# lcd-bracket.net
KiCad netlist of a schematic drawn in EAGLE
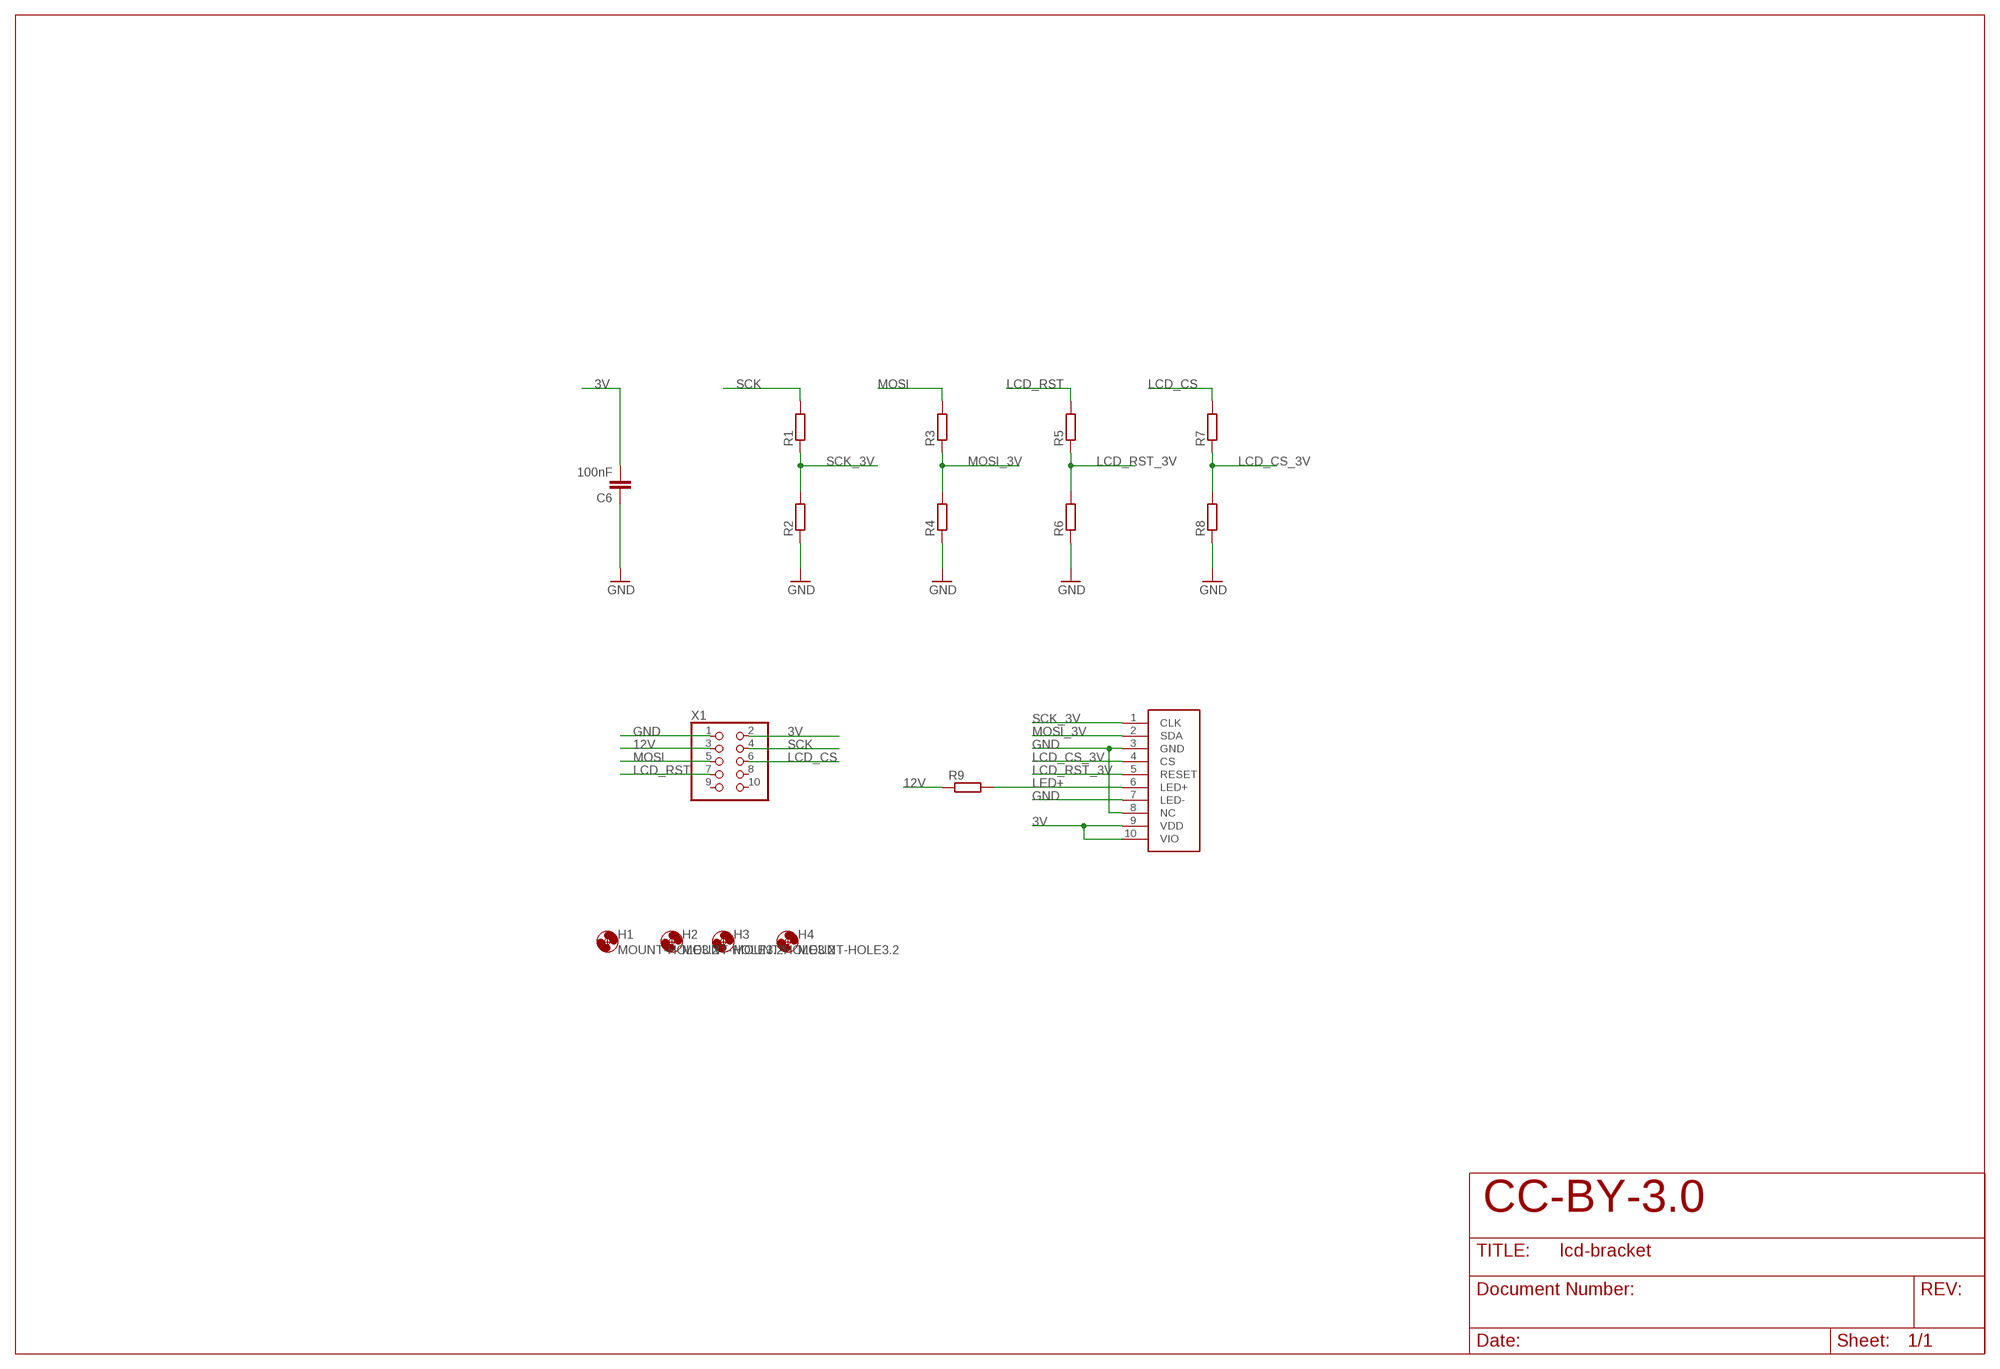
[diagram p0: schematic, sheet 1]

(export (version "E")
  (design (tool "Eeschema 10.0.6"))
  (components
    (comp (ref "C6")
      (value "100nF")
      (footprint "eagle-import:C0603K")
      (libsource (lib "eagle-import") (part "C-EUC0603K"))
    )
    (comp (ref "H1")
      (value "MOUNT-HOLE3.2")
      (footprint "eagle-import:3,2")
      (libsource (lib "eagle-import") (part "MOUNT-HOLE3.2"))
    )
    (comp (ref "H2")
      (value "MOUNT-HOLE3.2")
      (footprint "eagle-import:3,2")
      (libsource (lib "eagle-import") (part "MOUNT-HOLE3.2"))
    )
    (comp (ref "H3")
      (value "MOUNT-HOLE3.2")
      (footprint "eagle-import:3,2")
      (libsource (lib "eagle-import") (part "MOUNT-HOLE3.2"))
    )
    (comp (ref "H4")
      (value "MOUNT-HOLE3.2")
      (footprint "eagle-import:3,2")
      (libsource (lib "eagle-import") (part "MOUNT-HOLE3.2"))
    )
    (comp (ref "R1")
      (value "R-EU_R0603")
      (footprint "eagle-import:R0603")
      (libsource (lib "eagle-import") (part "R-EU_R0603"))
    )
    (comp (ref "R2")
      (value "R-EU_R0603")
      (footprint "eagle-import:R0603")
      (libsource (lib "eagle-import") (part "R-EU_R0603"))
    )
    (comp (ref "R3")
      (value "R-EU_R0603")
      (footprint "eagle-import:R0603")
      (libsource (lib "eagle-import") (part "R-EU_R0603"))
    )
    (comp (ref "R4")
      (value "R-EU_R0603")
      (footprint "eagle-import:R0603")
      (libsource (lib "eagle-import") (part "R-EU_R0603"))
    )
    (comp (ref "R5")
      (value "R-EU_R0603")
      (footprint "eagle-import:R0603")
      (libsource (lib "eagle-import") (part "R-EU_R0603"))
    )
    (comp (ref "R6")
      (value "R-EU_R0603")
      (footprint "eagle-import:R0603")
      (libsource (lib "eagle-import") (part "R-EU_R0603"))
    )
    (comp (ref "R7")
      (value "R-EU_R0603")
      (footprint "eagle-import:R0603")
      (libsource (lib "eagle-import") (part "R-EU_R0603"))
    )
    (comp (ref "R8")
      (value "R-EU_R0603")
      (footprint "eagle-import:R0603")
      (libsource (lib "eagle-import") (part "R-EU_R0603"))
    )
    (comp (ref "R9")
      (value "R-EU_R1206")
      (footprint "eagle-import:R1206")
      (libsource (lib "eagle-import") (part "R-EU_R1206"))
    )
    (comp (ref "X1")
      (value "PINHD-2X5")
      (footprint "eagle-import:2X05")
      (libsource (lib "eagle-import") (part "PINHD-2X5"))
    )
    (comp (ref "X2")
      (value "NOKIA")
      (footprint "eagle-import:DF23")
      (libsource (lib "eagle-import") (part "NOKIA"))
    )
  )
  (nets
    (net (code "1") (name "/3V") (class "Default")
      (node (ref "C6") (pin "2") (pinfunction "2_2") (pintype "passive"))
      (node (ref "X1") (pin "2") (pinfunction "2_2") (pintype "passive"))
      (node (ref "X2") (pin "10") (pinfunction "VIO_10") (pintype "bidirectional"))
      (node (ref "X2") (pin "9") (pinfunction "VDD_9") (pintype "bidirectional"))
    )
    (net (code "2") (name "/12V") (class "Default")
      (node (ref "R9") (pin "1") (pinfunction "1_1") (pintype "passive"))
      (node (ref "X1") (pin "3") (pinfunction "3_3") (pintype "passive"))
    )
    (net (code "3") (name "/LCD_CS") (class "Default")
      (node (ref "R7") (pin "2") (pinfunction "2_2") (pintype "passive"))
      (node (ref "X1") (pin "6") (pinfunction "6_6") (pintype "passive"))
    )
    (net (code "4") (name "/LCD_CS_3V") (class "Default")
      (node (ref "R7") (pin "1") (pinfunction "1_1") (pintype "passive"))
      (node (ref "R8") (pin "2") (pinfunction "2_2") (pintype "passive"))
      (node (ref "X2") (pin "4") (pinfunction "CS_4") (pintype "bidirectional"))
    )
    (net (code "5") (name "/LCD_RST") (class "Default")
      (node (ref "R5") (pin "2") (pinfunction "2_2") (pintype "passive"))
      (node (ref "X1") (pin "7") (pinfunction "7_7") (pintype "passive"))
    )
    (net (code "6") (name "/LCD_RST_3V") (class "Default")
      (node (ref "R5") (pin "1") (pinfunction "1_1") (pintype "passive"))
      (node (ref "R6") (pin "2") (pinfunction "2_2") (pintype "passive"))
      (node (ref "X2") (pin "5") (pinfunction "RESET_5") (pintype "bidirectional"))
    )
    (net (code "7") (name "/LED+") (class "Default")
      (node (ref "R9") (pin "2") (pinfunction "2_2") (pintype "passive"))
      (node (ref "X2") (pin "6") (pinfunction "LED+_6") (pintype "bidirectional"))
    )
    (net (code "8") (name "/MOSI") (class "Default")
      (node (ref "R3") (pin "2") (pinfunction "2_2") (pintype "passive"))
      (node (ref "X1") (pin "5") (pinfunction "5_5") (pintype "passive"))
    )
    (net (code "9") (name "/MOSI_3V") (class "Default")
      (node (ref "R3") (pin "1") (pinfunction "1_1") (pintype "passive"))
      (node (ref "R4") (pin "2") (pinfunction "2_2") (pintype "passive"))
      (node (ref "X2") (pin "2") (pinfunction "SDA_2") (pintype "bidirectional"))
    )
    (net (code "10") (name "/SCK") (class "Default")
      (node (ref "R1") (pin "2") (pinfunction "2_2") (pintype "passive"))
      (node (ref "X1") (pin "4") (pinfunction "4_4") (pintype "passive"))
    )
    (net (code "11") (name "/SCK_3V") (class "Default")
      (node (ref "R1") (pin "1") (pinfunction "1_1") (pintype "passive"))
      (node (ref "R2") (pin "2") (pinfunction "2_2") (pintype "passive"))
      (node (ref "X2") (pin "1") (pinfunction "CLK_1") (pintype "bidirectional"))
    )
    (net (code "12") (name "GND") (class "Default")
      (node (ref "C6") (pin "1") (pinfunction "1_1") (pintype "passive"))
      (node (ref "R2") (pin "1") (pinfunction "1_1") (pintype "passive"))
      (node (ref "R4") (pin "1") (pinfunction "1_1") (pintype "passive"))
      (node (ref "R6") (pin "1") (pinfunction "1_1") (pintype "passive"))
      (node (ref "R8") (pin "1") (pinfunction "1_1") (pintype "passive"))
      (node (ref "X1") (pin "1") (pinfunction "1_1") (pintype "passive"))
      (node (ref "X2") (pin "3") (pinfunction "GND_3") (pintype "bidirectional"))
      (node (ref "X2") (pin "7") (pinfunction "LED-_7") (pintype "bidirectional"))
      (node (ref "X2") (pin "8") (pinfunction "NC_8") (pintype "bidirectional"))
    )
    (net (code "13") (name "unconnected-(X1-Pad8)") (class "Default")
      (node (ref "X1") (pin "8") (pinfunction "8_8") (pintype "passive"))
    )
    (net (code "14") (name "unconnected-(X1-Pad9)") (class "Default")
      (node (ref "X1") (pin "9") (pinfunction "9_9") (pintype "passive"))
    )
    (net (code "15") (name "unconnected-(X1-Pad10)") (class "Default")
      (node (ref "X1") (pin "10") (pinfunction "10_10") (pintype "passive"))
    )
  )
)
